# RaceSCH.net
KiCad netlist of a schematic drawn in Altium Designer
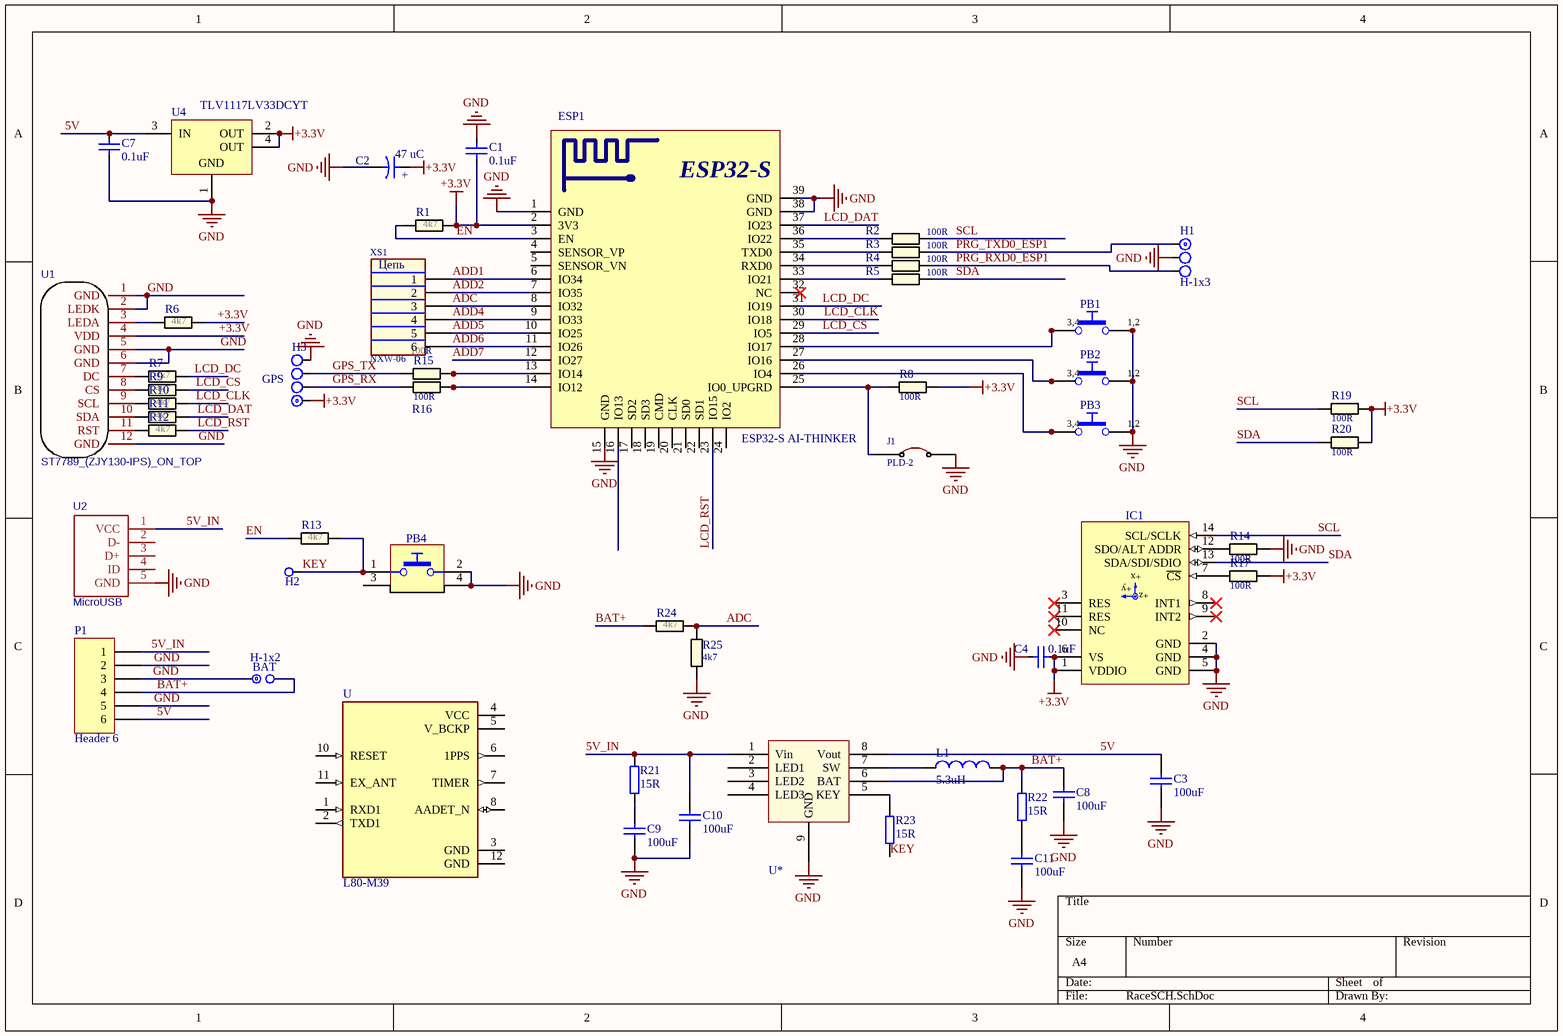
[diagram p0: RaceSCH.SchDoc]

(export (version "E")
  (design (tool "Eeschema 10.0.6"))
  (components
    (comp (ref "BAT") (value "H-1x2") (footprint "J1x2") (libsource (lib "Connektor") (part "H-1x2")))
    (comp (ref "C1")
      (value "0.1uF")
      (footprint "C0603")
      (description "Конденсатор")
      (libsource (lib "LoadControl") (part "CAPACITOR"))
    )
    (comp (ref "C2")
      (value "47 uC")
      (footprint "CAPMP3528X210N")
      (description "Polarised capacitor")
      (fields
        (field (name "PART NUMBER") "CTE3528-21_100UF_6.3V_10%")
        (field (name "VOLTAGE") "6.3V")
        (field (name "AUTHOR") "CERN DEM JLC")
      )
      (libsource (lib "Capacitors") (part "Capacitor - polarized"))
    )
    (comp (ref "C3")
      (value "100uF")
      (footprint "CAP1210")
      (description "CAP SM 1210 X5R 100uF 6.3V 10%")
      (fields
        (field (name "PART NUMBER") "CAP-SM-1210-X5R-100uF-6.3V")
        (field (name "MANUFACTURER") "GENERIC")
      )
      (libsource (lib "electronpowered") (part "CAP"))
    )
    (comp (ref "C4")
      (value "0.1uF")
      (footprint "C0603")
      (description "Конденсатор")
      (libsource (lib "LoadControl") (part "CAPACITOR"))
    )
    (comp (ref "C7")
      (value "0.1uF")
      (footprint "C0603")
      (description "Конденсатор")
      (libsource (lib "LoadControl") (part "CAPACITOR"))
    )
    (comp (ref "C8")
      (value "100uF")
      (footprint "CAP1210")
      (description "CAP SM 1210 X5R 100uF 6.3V 10%")
      (fields
        (field (name "PART NUMBER") "CAP-SM-1210-X5R-100uF-6.3V")
        (field (name "MANUFACTURER") "GENERIC")
      )
      (libsource (lib "electronpowered") (part "CAP"))
    )
    (comp (ref "C9")
      (value "100uF")
      (footprint "CAP1210")
      (description "CAP SM 1210 X5R 100uF 6.3V 10%")
      (fields
        (field (name "PART NUMBER") "CAP-SM-1210-X5R-100uF-6.3V")
        (field (name "MANUFACTURER") "GENERIC")
      )
      (libsource (lib "electronpowered") (part "CAP"))
    )
    (comp (ref "C10")
      (value "100uF")
      (footprint "CAP1210")
      (description "CAP SM 1210 X5R 100uF 6.3V 10%")
      (fields
        (field (name "PART NUMBER") "CAP-SM-1210-X5R-100uF-6.3V")
        (field (name "MANUFACTURER") "GENERIC")
      )
      (libsource (lib "electronpowered") (part "CAP"))
    )
    (comp (ref "C11")
      (value "100uF")
      (footprint "CAP1210")
      (description "CAP SM 1210 X5R 100uF 6.3V 10%")
      (fields
        (field (name "PART NUMBER") "CAP-SM-1210-X5R-100uF-6.3V")
        (field (name "MANUFACTURER") "GENERIC")
      )
      (libsource (lib "electronpowered") (part "CAP"))
    )
    (comp (ref "ESP1")
      (value "ESP32-S AI-THINKER")
      (footprint "ESP32-S")
      (description "Wi-Fi module")
      (libsource (lib "LoadControl") (part "ESP32-S AI-THINKER"))
    )
    (comp (ref "H1") (value "H-1x3") (footprint "J1x3") (libsource (lib "Connektor") (part "H-1x3")))
    (comp (ref "H2") (value "H-1") (footprint "J1") (libsource (lib "Connektor") (part "H-1")))
    (comp (ref "H3") (value "GPS") (footprint "J1x4") (libsource (lib "Connektor") (part "H-1x4")))
    (comp (ref "IC1")
      (value "ADXL343BCCZ")
      (footprint "ANALOG-DEVICES_CC-14-1")
      (description "3-Axis, ±2g/±4g/±8g/±16g Digital MEMS Accelerometer")
      (fields (field (name "MANUFACTURER") "ANALOG DEVICES") (field (name "AUTHOR") "CERN DEM JLC"))
      (libsource (lib "ICs And Semiconductors") (part "ADXL343"))
    )
    (comp (ref "J1") (value "PLD-2") (footprint "PLD-2") (libsource (lib "LoadControl") (part "PLD-2")))
    (comp (ref "L1")
      (value "5.3uH")
      (footprint "SRR5028-4R2Y")
      (fields (field (name "Comment") "INDUCTOR_2"))
      (libsource (lib "FlowMetter") (part "INDUCTOR_2"))
    )
    (comp (ref "P1")
      (value "Header 6")
      (footprint "HDR1X6")
      (description "Header, 6-Pin")
      (fields (field (name "PUBLISHER") "Altium Limited"))
      (libsource (lib "Miscellaneous Connectors") (part "Header 6"))
    )
    (comp (ref "PB1")
      (value "Push Button")
      (footprint "PB_OMRON_B3F-1000")
      (description "Push-Button Switch SPDT")
      (fields
        (field (name "PART NUMBER") "PB_OMRON_B3F-1000")
        (field (name "MANUFACTURER") "OMRON")
        (field (name "AUTHOR") "CERN DEM JMW")
      )
      (libsource (lib "Eletro-mechanical") (part "PB SPST 12NO-34NO"))
    )
    (comp (ref "PB2")
      (value "Push Button")
      (footprint "PB_OMRON_B3F-1000")
      (description "Push-Button Switch SPDT")
      (fields
        (field (name "PART NUMBER") "PB_OMRON_B3F-1000")
        (field (name "MANUFACTURER") "OMRON")
        (field (name "AUTHOR") "CERN DEM JMW")
      )
      (libsource (lib "Eletro-mechanical") (part "PB SPST 12NO-34NO"))
    )
    (comp (ref "PB3")
      (value "Push Button")
      (footprint "PB_OMRON_B3F-1000")
      (description "Push-Button Switch SPDT")
      (fields
        (field (name "PART NUMBER") "PB_OMRON_B3F-1000")
        (field (name "MANUFACTURER") "OMRON")
        (field (name "AUTHOR") "CERN DEM JMW")
      )
      (libsource (lib "Eletro-mechanical") (part "PB SPST 12NO-34NO"))
    )
    (comp (ref "PB4")
      (value "Push Button")
      (footprint "PB_ALPS_SKHHLQA010")
      (description "Push-Button Switch SPDT")
      (fields
        (field (name "PART NUMBER") "PB_ALPS_SKHHLQA010")
        (field (name "MANUFACTURER") "ALPS")
        (field (name "AUTHOR") "CERN DEM JLC")
      )
      (libsource (lib "Eletro-mechanical") (part "PB SPST 1NO-2NO 34CASE"))
    )
    (comp (ref "R1")
      (value "4k7")
      (footprint "R0603(1608)")
      (description "Resistor")
      (fields (field (name "Comment") "RESISTOR"))
      (libsource (lib "") (part "RESISTOR_1"))
    )
    (comp (ref "R2")
      (value "100R")
      (footprint "R0603(1608)")
      (description "Resistor")
      (fields (field (name "Comment") "RESISTOR"))
      (libsource (lib "") (part "RESISTOR_2"))
    )
    (comp (ref "R3")
      (value "100R")
      (footprint "R0603(1608)")
      (description "Resistor")
      (fields (field (name "Comment") "RESISTOR"))
      (libsource (lib "") (part "RESISTOR_2"))
    )
    (comp (ref "R4")
      (value "100R")
      (footprint "R0603(1608)")
      (description "Resistor")
      (fields (field (name "Comment") "RESISTOR"))
      (libsource (lib "") (part "RESISTOR_2"))
    )
    (comp (ref "R5")
      (value "100R")
      (footprint "R0603(1608)")
      (description "Resistor")
      (fields (field (name "Comment") "RESISTOR"))
      (libsource (lib "") (part "RESISTOR_2"))
    )
    (comp (ref "R6")
      (value "4k7")
      (footprint "R0603(1608)")
      (description "Resistor")
      (fields (field (name "Comment") "RESISTOR"))
      (libsource (lib "") (part "RESISTOR_1"))
    )
    (comp (ref "R7")
      (value "4k7")
      (footprint "R0603(1608)")
      (description "Resistor")
      (fields (field (name "Comment") "RESISTOR"))
      (libsource (lib "") (part "RESISTOR_1"))
    )
    (comp (ref "R8")
      (value "100R")
      (footprint "R0603(1608)")
      (description "Resistor")
      (fields (field (name "Comment") "RESISTOR"))
      (libsource (lib "") (part "RESISTOR_1"))
    )
    (comp (ref "R9")
      (value "4k7")
      (footprint "R0603(1608)")
      (description "Resistor")
      (fields (field (name "Comment") "RESISTOR"))
      (libsource (lib "") (part "RESISTOR_1"))
    )
    (comp (ref "R10")
      (value "4k7")
      (footprint "R0603(1608)")
      (description "Resistor")
      (fields (field (name "Comment") "RESISTOR"))
      (libsource (lib "") (part "RESISTOR_1"))
    )
    (comp (ref "R11")
      (value "4k7")
      (footprint "R0603(1608)")
      (description "Resistor")
      (fields (field (name "Comment") "RESISTOR"))
      (libsource (lib "") (part "RESISTOR_1"))
    )
    (comp (ref "R12")
      (value "4k7")
      (footprint "R0603(1608)")
      (description "Resistor")
      (fields (field (name "Comment") "RESISTOR"))
      (libsource (lib "") (part "RESISTOR_1"))
    )
    (comp (ref "R13")
      (value "4k7")
      (footprint "R0603(1608)")
      (description "Resistor")
      (fields (field (name "Comment") "RESISTOR"))
      (libsource (lib "") (part "RESISTOR_1"))
    )
    (comp (ref "R14")
      (value "100R")
      (footprint "R0603(1608)")
      (description "Resistor")
      (fields (field (name "Comment") "RESISTOR"))
      (libsource (lib "") (part "RESISTOR_3"))
    )
    (comp (ref "R15")
      (value "100R")
      (footprint "R0603(1608)")
      (description "Resistor")
      (fields (field (name "Comment") "RESISTOR"))
      (libsource (lib "LoadControl") (part "RESISTOR"))
    )
    (comp (ref "R16")
      (value "100R")
      (footprint "R0603(1608)")
      (description "Resistor")
      (fields (field (name "Comment") "RESISTOR"))
      (libsource (lib "LoadControl") (part "RESISTOR"))
    )
    (comp (ref "R17")
      (value "100R")
      (footprint "R0603(1608)")
      (description "Resistor")
      (fields (field (name "Comment") "RESISTOR"))
      (libsource (lib "") (part "RESISTOR_1"))
    )
    (comp (ref "R19")
      (value "100R")
      (footprint "R0603(1608)")
      (description "Resistor")
      (fields (field (name "Comment") "RESISTOR"))
      (libsource (lib "") (part "RESISTOR_3"))
    )
    (comp (ref "R20")
      (value "100R")
      (footprint "R0603(1608)")
      (description "Resistor")
      (fields (field (name "Comment") "RESISTOR"))
      (libsource (lib "") (part "RESISTOR_3"))
    )
    (comp (ref "R21")
      (value "15R")
      (footprint "RES0603")
      (description "RES SM 0603 15R")
      (fields (field (name "PART NUMBER") "RES-SM-0603-15R") (field (name "MANUFACTURER") "GENERIC"))
      (libsource (lib "electronpowered") (part "RES"))
    )
    (comp (ref "R22")
      (value "15R")
      (footprint "RES0603")
      (description "RES SM 0603 15R")
      (fields (field (name "PART NUMBER") "RES-SM-0603-15R") (field (name "MANUFACTURER") "GENERIC"))
      (libsource (lib "electronpowered") (part "RES"))
    )
    (comp (ref "R23")
      (value "15R")
      (footprint "RES0603")
      (description "RES SM 0603 15R")
      (fields (field (name "PART NUMBER") "RES-SM-0603-15R") (field (name "MANUFACTURER") "GENERIC"))
      (libsource (lib "electronpowered") (part "RES"))
    )
    (comp (ref "R24")
      (value "4k7")
      (footprint "R0603(1608)")
      (description "Resistor")
      (fields (field (name "Comment") "RESISTOR"))
      (libsource (lib "") (part "RESISTOR_1"))
    )
    (comp (ref "R25")
      (value "4k7")
      (footprint "R0603(1608)")
      (description "Resistor")
      (fields (field (name "Comment") "RESISTOR"))
      (libsource (lib "LoadControl") (part "RESISTOR"))
    )
    (comp (ref "U")
      (value "L80-M39")
      (footprint "XCVR_L80-M39")
      (fields (field (name "MF") "Quectel"))
      (libsource (lib "L80-M39") (part "L80-M39"))
    )
    (comp (ref "U*")
      (value "IP5306")
      (footprint "IP5306_GND")
      (description "2.1A_lipo_CHARGER")
      (libsource (lib "MyLib") (part "IP5306"))
    )
    (comp (ref "U1")
      (value "ST7789_(ZJY130-IPS)_ON_TOP")
      (footprint "ST7789_ON_TOP")
      (fields
        (field (name "BOM_MANUFACTURER PART") "?")
        (field (name "BOM_SUPPLIER PART") "undefined")
        (field (name "CONTRIBUTOR") "§°§Э§Ц§Ф §¬§а§б§Ц§Ы§Ь§Ъ§Я")
      )
      (libsource (lib "LCD_LIB") (part "ST7789_(ZJY130-IPS)_ON_TOP copy"))
    )
    (comp (ref "U2")
      (value "MicroUSB")
      (footprint "MICROUSB")
      (fields (field (name "BOM_MANUFACTURER PART") "?") (field (name "CONTRIBUTOR") "SparkFun"))
      (libsource (lib "LCD_LIB") (part "MicroUSB"))
    )
    (comp (ref "U4")
      (value "TLV1117LV33DCYT")
      (footprint "TI-DCY4_N")
      (fields (field (name "MANUFACTURER") "Texas Instruments"))
      (libsource (lib "FlowMetter") (part "TLV1117LV30DCYT"))
    )
    (comp (ref "XS1")
      (value "NXW-06")
      (footprint "NXW-06")
      (description "2.0mm pitch")
      (libsource (lib "FlowMetter") (part "NXW-06"))
    )
  )
  (nets
    (net (code "1") (name "+3.3V") (class "Default")
      (node (ref "C1") (pin "2") (pinfunction "2_2") (pintype "passive"))
      (node (ref "C2") (pin "1") (pinfunction "1_1") (pintype "passive"))
      (node (ref "C4") (pin "1") (pinfunction "1_1") (pintype "passive"))
      (node (ref "ESP1") (pin "2") (pinfunction "3V3_2") (pintype "passive"))
      (node (ref "H3") (pin "1") (pinfunction "1_1") (pintype "passive"))
      (node (ref "IC1") (pin "1") (pinfunction "VDDIO_1") (pintype "power_in"))
      (node (ref "IC1") (pin "6") (pinfunction "VS_6") (pintype "power_in"))
      (node (ref "R1") (pin "2") (pintype "passive"))
      (node (ref "R17") (pin "2") (pintype "passive"))
      (node (ref "R19") (pin "1") (pintype "passive"))
      (node (ref "R20") (pin "1") (pintype "passive"))
      (node (ref "R6") (pin "2") (pintype "passive"))
      (node (ref "R8") (pin "2") (pintype "passive"))
      (node (ref "U1") (pin "4") (pinfunction "VDD_4") (pintype "passive"))
      (node (ref "U4") (pin "2") (pinfunction "OUT_2") (pintype "power_in"))
      (node (ref "U4") (pin "4") (pinfunction "OUT_4") (pintype "power_in"))
    )
    (net (code "2") (name "/5V") (class "Default")
      (node (ref "C3") (pin "2") (pinfunction "2_2") (pintype "passive"))
      (node (ref "C7") (pin "1") (pinfunction "1_1") (pintype "passive"))
      (node (ref "P1") (pin "6") (pinfunction "6_6") (pintype "passive"))
      (node (ref "U*") (pin "8") (pinfunction "Vout_8") (pintype "passive"))
      (node (ref "U4") (pin "3") (pinfunction "IN_3") (pintype "power_in"))
    )
    (net (code "3") (name "/5V_IN") (class "Default")
      (node (ref "C10") (pin "2") (pinfunction "2_2") (pintype "passive"))
      (node (ref "P1") (pin "1") (pinfunction "1_1") (pintype "passive"))
      (node (ref "R21") (pin "2") (pinfunction "2_2") (pintype "passive"))
      (node (ref "U*") (pin "1") (pinfunction "Vin_1") (pintype "passive"))
      (node (ref "U2") (pin "1") (pinfunction "VCC_1") (pintype "passive"))
    )
    (net (code "4") (name "/ADC") (class "Default")
      (node (ref "ESP1") (pin "8") (pinfunction "IO32_8") (pintype "power_in"))
      (node (ref "R24") (pin "2") (pintype "passive"))
      (node (ref "R25") (pin "2") (pintype "passive"))
      (node (ref "XS1") (pin "3") (pinfunction "3_3") (pintype "passive"))
    )
    (net (code "5") (name "/ADD1") (class "Default")
      (node (ref "ESP1") (pin "6") (pinfunction "IO34_6") (pintype "passive"))
      (node (ref "XS1") (pin "1") (pinfunction "1_1") (pintype "passive"))
    )
    (net (code "6") (name "/ADD2") (class "Default")
      (node (ref "ESP1") (pin "7") (pinfunction "IO35_7") (pintype "passive"))
      (node (ref "XS1") (pin "2") (pinfunction "2_2") (pintype "passive"))
    )
    (net (code "7") (name "/ADD4") (class "Default")
      (node (ref "ESP1") (pin "9") (pinfunction "IO33_9") (pintype "power_in"))
      (node (ref "XS1") (pin "4") (pinfunction "4_4") (pintype "passive"))
    )
    (net (code "8") (name "/ADD5") (class "Default")
      (node (ref "ESP1") (pin "10") (pinfunction "IO25_10") (pintype "power_in"))
      (node (ref "XS1") (pin "5") (pinfunction "5_5") (pintype "passive"))
    )
    (net (code "9") (name "/ADD6") (class "Default")
      (node (ref "ESP1") (pin "11") (pinfunction "IO26_11") (pintype "power_in"))
      (node (ref "XS1") (pin "6") (pinfunction "6_6") (pintype "passive"))
    )
    (net (code "10") (name "/ADD7") (class "Default")
      (node (ref "ESP1") (pin "12") (pinfunction "IO27_12") (pintype "power_in"))
    )
    (net (code "11") (name "/BAT+") (class "Default")
      (node (ref "BAT") (pin "2") (pinfunction "2_2") (pintype "passive"))
      (node (ref "C8") (pin "2") (pinfunction "2_2") (pintype "passive"))
      (node (ref "L1") (pin "2") (pinfunction "2_2") (pintype "passive"))
      (node (ref "P1") (pin "4") (pinfunction "4_4") (pintype "passive"))
      (node (ref "R22") (pin "2") (pinfunction "2_2") (pintype "passive"))
      (node (ref "R24") (pin "1") (pintype "passive"))
      (node (ref "U*") (pin "6") (pinfunction "BAT_6") (pintype "passive"))
    )
    (net (code "12") (name "/EN") (class "Default")
      (node (ref "ESP1") (pin "3") (pinfunction "EN_3") (pintype "passive"))
      (node (ref "R1") (pin "1") (pintype "passive"))
      (node (ref "R13") (pin "1") (pintype "passive"))
    )
    (net (code "13") (name "/GPS_RX") (class "Default")
      (node (ref "H3") (pin "2") (pinfunction "2_2") (pintype "passive"))
      (node (ref "R16") (pin "1") (pintype "passive"))
    )
    (net (code "14") (name "/GPS_TX") (class "Default")
      (node (ref "H3") (pin "3") (pinfunction "3_3") (pintype "passive"))
      (node (ref "R15") (pin "1") (pintype "passive"))
    )
    (net (code "15") (name "/KEY") (class "Default")
      (node (ref "H2") (pin "1") (pinfunction "1_1") (pintype "passive"))
      (node (ref "PB4") (pin "1") (pinfunction "1_1") (pintype "passive"))
      (node (ref "R13") (pin "2") (pintype "passive"))
      (node (ref "R23") (pin "1") (pinfunction "1_1") (pintype "passive"))
    )
    (net (code "16") (name "/LCD_CLK") (class "Default")
      (node (ref "ESP1") (pin "30") (pinfunction "IO18_30") (pintype "power_in"))
      (node (ref "R10") (pin "2") (pintype "passive"))
    )
    (net (code "17") (name "/LCD_CS") (class "Default")
      (node (ref "ESP1") (pin "29") (pinfunction "IO5_29") (pintype "power_in"))
      (node (ref "R9") (pin "2") (pintype "passive"))
    )
    (net (code "18") (name "/LCD_DAT") (class "Default")
      (node (ref "ESP1") (pin "37") (pinfunction "IO23_37") (pintype "power_in"))
      (node (ref "R11") (pin "2") (pintype "passive"))
    )
    (net (code "19") (name "/LCD_DC") (class "Default")
      (node (ref "ESP1") (pin "31") (pinfunction "IO19_31") (pintype "power_in"))
      (node (ref "R7") (pin "2") (pintype "passive"))
    )
    (net (code "20") (name "/LCD_RST") (class "Default")
      (node (ref "ESP1") (pin "23") (pinfunction "IO15_23") (pintype "power_in"))
      (node (ref "R12") (pin "2") (pintype "passive"))
    )
    (net (code "21") (name "/PRG_RXD0_ESP1") (class "Default")
      (node (ref "H1") (pin "3") (pinfunction "3_3") (pintype "passive"))
      (node (ref "R4") (pin "1") (pintype "passive"))
    )
    (net (code "22") (name "/PRG_TXD0_ESP1") (class "Default")
      (node (ref "H1") (pin "1") (pinfunction "1_1") (pintype "passive"))
      (node (ref "R3") (pin "1") (pintype "passive"))
    )
    (net (code "23") (name "/SCL") (class "Default")
      (node (ref "IC1") (pin "14") (pinfunction "SCL/SCLK_14") (pintype "input"))
      (node (ref "R19") (pin "2") (pintype "passive"))
      (node (ref "R2") (pin "1") (pintype "passive"))
    )
    (net (code "24") (name "/SDA") (class "Default")
      (node (ref "IC1") (pin "13") (pinfunction "SDA/SDI/SDIO_13") (pintype "bidirectional"))
      (node (ref "R20") (pin "2") (pintype "passive"))
      (node (ref "R5") (pin "1") (pintype "passive"))
    )
    (net (code "25") (name "GND") (class "Default")
      (node (ref "BAT") (pin "1") (pinfunction "1_1") (pintype "passive"))
      (node (ref "C1") (pin "1") (pinfunction "1_1") (pintype "passive"))
      (node (ref "C10") (pin "1") (pinfunction "1_1") (pintype "passive"))
      (node (ref "C11") (pin "1") (pinfunction "1_1") (pintype "passive"))
      (node (ref "C2") (pin "2") (pinfunction "2_2") (pintype "passive"))
      (node (ref "C3") (pin "1") (pinfunction "1_1") (pintype "passive"))
      (node (ref "C4") (pin "2") (pinfunction "2_2") (pintype "passive"))
      (node (ref "C7") (pin "2") (pinfunction "2_2") (pintype "passive"))
      (node (ref "C8") (pin "1") (pinfunction "1_1") (pintype "passive"))
      (node (ref "C9") (pin "1") (pinfunction "1_1") (pintype "passive"))
      (node (ref "ESP1") (pin "1") (pinfunction "GND_1") (pintype "passive"))
      (node (ref "ESP1") (pin "15") (pinfunction "GND_15") (pintype "power_in"))
      (node (ref "ESP1") (pin "38") (pinfunction "GND_38") (pintype "power_in"))
      (node (ref "ESP1") (pin "39") (pinfunction "GND_39") (pintype "power_in"))
      (node (ref "H1") (pin "2") (pinfunction "2_2") (pintype "passive"))
      (node (ref "H3") (pin "4") (pinfunction "4_4") (pintype "passive"))
      (node (ref "IC1") (pin "2") (pinfunction "GND_2") (pintype "power_in"))
      (node (ref "IC1") (pin "4") (pinfunction "GND_4") (pintype "power_in"))
      (node (ref "IC1") (pin "5") (pinfunction "GND_5") (pintype "power_in"))
      (node (ref "J1") (pin "2") (pinfunction "2_2") (pintype "power_in"))
      (node (ref "P1") (pin "2") (pinfunction "2_2") (pintype "passive"))
      (node (ref "P1") (pin "3") (pinfunction "3_3") (pintype "passive"))
      (node (ref "P1") (pin "5") (pinfunction "5_5") (pintype "passive"))
      (node (ref "PB1") (pin "1") (pinfunction "1_1") (pintype "passive"))
      (node (ref "PB1") (pin "2") (pinfunction "2_2") (pintype "passive"))
      (node (ref "PB2") (pin "1") (pinfunction "1_1") (pintype "passive"))
      (node (ref "PB2") (pin "2") (pinfunction "2_2") (pintype "passive"))
      (node (ref "PB3") (pin "1") (pinfunction "1_1") (pintype "passive"))
      (node (ref "PB3") (pin "2") (pinfunction "2_2") (pintype "passive"))
      (node (ref "PB4") (pin "2") (pinfunction "2_2") (pintype "passive"))
      (node (ref "PB4") (pin "4") (pinfunction "4_4") (pintype "passive"))
      (node (ref "R14") (pin "1") (pintype "passive"))
      (node (ref "R25") (pin "1") (pintype "passive"))
      (node (ref "U*") (pin "9") (pinfunction "GND_9") (pintype "passive"))
      (node (ref "U1") (pin "1") (pinfunction "GND_1") (pintype "passive"))
      (node (ref "U1") (pin "12") (pinfunction "GND_12") (pintype "passive"))
      (node (ref "U1") (pin "2") (pinfunction "LEDK_2") (pintype "passive"))
      (node (ref "U1") (pin "5") (pinfunction "GND_5") (pintype "passive"))
      (node (ref "U1") (pin "6") (pinfunction "GND_6") (pintype "passive"))
      (node (ref "U2") (pin "5") (pinfunction "GND_5") (pintype "passive"))
      (node (ref "U4") (pin "1") (pinfunction "GND_1") (pintype "power_in"))
    )
    (net (code "26") (name "Net-(C9-Pad2)") (class "Default")
      (node (ref "C9") (pin "2") (pinfunction "2_2") (pintype "passive"))
      (node (ref "R21") (pin "1") (pinfunction "1_1") (pintype "passive"))
    )
    (net (code "27") (name "Net-(C11-Pad2)") (class "Default")
      (node (ref "C11") (pin "2") (pinfunction "2_2") (pintype "passive"))
      (node (ref "R22") (pin "1") (pinfunction "1_1") (pintype "passive"))
    )
    (net (code "28") (name "Net-(ESP1-IO0_UPGRD)") (class "Default")
      (node (ref "ESP1") (pin "25") (pinfunction "IO0_UPGRD_25") (pintype "power_in"))
      (node (ref "J1") (pin "1") (pinfunction "1_1") (pintype "power_in"))
      (node (ref "R8") (pin "1") (pintype "passive"))
    )
    (net (code "29") (name "Net-(ESP1-IO4)") (class "Default")
      (node (ref "ESP1") (pin "26") (pinfunction "IO4_26") (pintype "power_in"))
      (node (ref "PB3") (pin "3") (pinfunction "3_3") (pintype "passive"))
      (node (ref "PB3") (pin "4") (pinfunction "4_4") (pintype "passive"))
    )
    (net (code "30") (name "Net-(ESP1-IO12)") (class "Default")
      (node (ref "ESP1") (pin "14") (pinfunction "IO12_14") (pintype "power_in"))
      (node (ref "R16") (pin "2") (pintype "passive"))
    )
    (net (code "31") (name "Net-(ESP1-IO14)") (class "Default")
      (node (ref "ESP1") (pin "13") (pinfunction "IO14_13") (pintype "power_in"))
      (node (ref "R15") (pin "2") (pintype "passive"))
    )
    (net (code "32") (name "Net-(ESP1-IO16)") (class "Default")
      (node (ref "ESP1") (pin "27") (pinfunction "IO16_27") (pintype "power_in"))
      (node (ref "PB2") (pin "3") (pinfunction "3_3") (pintype "passive"))
      (node (ref "PB2") (pin "4") (pinfunction "4_4") (pintype "passive"))
    )
    (net (code "33") (name "Net-(ESP1-IO17)") (class "Default")
      (node (ref "ESP1") (pin "28") (pinfunction "IO17_28") (pintype "power_in"))
      (node (ref "PB1") (pin "3") (pinfunction "3_3") (pintype "passive"))
      (node (ref "PB1") (pin "4") (pinfunction "4_4") (pintype "passive"))
    )
    (net (code "34") (name "Net-(ESP1-IO21)") (class "Default")
      (node (ref "ESP1") (pin "33") (pinfunction "IO21_33") (pintype "power_in"))
      (node (ref "R5") (pin "2") (pintype "passive"))
    )
    (net (code "35") (name "Net-(ESP1-IO22)") (class "Default")
      (node (ref "ESP1") (pin "36") (pinfunction "IO22_36") (pintype "power_in"))
      (node (ref "R2") (pin "2") (pintype "passive"))
    )
    (net (code "36") (name "Net-(ESP1-RXD0)") (class "Default")
      (node (ref "ESP1") (pin "34") (pinfunction "RXD0_34") (pintype "power_in"))
      (node (ref "R4") (pin "2") (pintype "passive"))
    )
    (net (code "37") (name "Net-(ESP1-TXD0)") (class "Default")
      (node (ref "ESP1") (pin "35") (pinfunction "TXD0_35") (pintype "power_in"))
      (node (ref "R3") (pin "2") (pintype "passive"))
    )
    (net (code "38") (name "Net-(IC1-SDO{slash}ALT_ADDR)") (class "Default")
      (node (ref "IC1") (pin "12") (pinfunction "SDO/ALT_ADDR_12") (pintype "bidirectional"))
      (node (ref "R14") (pin "2") (pintype "passive"))
    )
    (net (code "39") (name "Net-(IC1-~{CS})") (class "Default")
      (node (ref "IC1") (pin "7") (pinfunction "~{CS}_7") (pintype "input"))
      (node (ref "R17") (pin "1") (pintype "passive"))
    )
    (net (code "40") (name "Net-(U*-KEY)") (class "Default")
      (node (ref "R23") (pin "2") (pinfunction "2_2") (pintype "passive"))
      (node (ref "U*") (pin "5") (pinfunction "KEY_5") (pintype "passive"))
    )
    (net (code "41") (name "Net-(U*-SW)") (class "Default")
      (node (ref "L1") (pin "1") (pinfunction "1_1") (pintype "passive"))
      (node (ref "U*") (pin "7") (pinfunction "SW_7") (pintype "passive"))
    )
    (net (code "42") (name "Net-(U1-CS)") (class "Default")
      (node (ref "R9") (pin "1") (pintype "passive"))
      (node (ref "U1") (pin "8") (pinfunction "CS_8") (pintype "passive"))
    )
    (net (code "43") (name "Net-(U1-DC)") (class "Default")
      (node (ref "R7") (pin "1") (pintype "passive"))
      (node (ref "U1") (pin "7") (pinfunction "DC_7") (pintype "passive"))
    )
    (net (code "44") (name "Net-(U1-LEDA)") (class "Default")
      (node (ref "R6") (pin "1") (pintype "passive"))
      (node (ref "U1") (pin "3") (pinfunction "LEDA_3") (pintype "passive"))
    )
    (net (code "45") (name "Net-(U1-RST)") (class "Default")
      (node (ref "R12") (pin "1") (pintype "passive"))
      (node (ref "U1") (pin "11") (pinfunction "RST_11") (pintype "passive"))
    )
    (net (code "46") (name "Net-(U1-SCL)") (class "Default")
      (node (ref "R10") (pin "1") (pintype "passive"))
      (node (ref "U1") (pin "9") (pinfunction "SCL_9") (pintype "passive"))
    )
    (net (code "47") (name "Net-(U1-SDA)") (class "Default")
      (node (ref "R11") (pin "1") (pintype "passive"))
      (node (ref "U1") (pin "10") (pinfunction "SDA_10") (pintype "passive"))
    )
    (net (code "48") (name "unconnected-(ESP1-CLK-Pad20)") (class "Default")
      (node (ref "ESP1") (pin "20") (pinfunction "CLK_20") (pintype "power_in"))
    )
    (net (code "49") (name "unconnected-(ESP1-CMD-Pad19)") (class "Default")
      (node (ref "ESP1") (pin "19") (pinfunction "CMD_19") (pintype "power_in"))
    )
    (net (code "50") (name "unconnected-(ESP1-IO2-Pad24)") (class "Default")
      (node (ref "ESP1") (pin "24") (pinfunction "IO2_24") (pintype "power_in"))
    )
    (net (code "51") (name "unconnected-(ESP1-IO13-Pad16)") (class "Default")
      (node (ref "ESP1") (pin "16") (pinfunction "IO13_16") (pintype "power_in"))
    )
    (net (code "52") (name "unconnected-(ESP1-NC-Pad32)") (class "Default")
      (node (ref "ESP1") (pin "32") (pinfunction "NC_32") (pintype "power_in+no_connect"))
    )
    (net (code "53") (name "unconnected-(ESP1-SD0-Pad21)") (class "Default")
      (node (ref "ESP1") (pin "21") (pinfunction "SD0_21") (pintype "power_in"))
    )
    (net (code "54") (name "unconnected-(ESP1-SD1-Pad22)") (class "Default")
      (node (ref "ESP1") (pin "22") (pinfunction "SD1_22") (pintype "power_in"))
    )
    (net (code "55") (name "unconnected-(ESP1-SD2-Pad17)") (class "Default")
      (node (ref "ESP1") (pin "17") (pinfunction "SD2_17") (pintype "power_in"))
    )
    (net (code "56") (name "unconnected-(ESP1-SD3-Pad18)") (class "Default")
      (node (ref "ESP1") (pin "18") (pinfunction "SD3_18") (pintype "power_in"))
    )
    (net (code "57") (name "unconnected-(ESP1-SENSOR_VN-Pad5)") (class "Default")
      (node (ref "ESP1") (pin "5") (pinfunction "SENSOR_VN_5") (pintype "passive"))
    )
    (net (code "58") (name "unconnected-(ESP1-SENSOR_VP-Pad4)") (class "Default")
      (node (ref "ESP1") (pin "4") (pinfunction "SENSOR_VP_4") (pintype "passive"))
    )
    (net (code "59") (name "unconnected-(IC1-INT1-Pad8)") (class "Default")
      (node (ref "IC1") (pin "8") (pinfunction "INT1_8") (pintype "output+no_connect"))
    )
    (net (code "60") (name "unconnected-(IC1-INT2-Pad9)") (class "Default")
      (node (ref "IC1") (pin "9") (pinfunction "INT2_9") (pintype "output+no_connect"))
    )
    (net (code "61") (name "unconnected-(IC1-NC-Pad10)") (class "Default")
      (node (ref "IC1") (pin "10") (pinfunction "NC_10") (pintype "passive+no_connect"))
    )
    (net (code "62") (name "unconnected-(IC1-RES-Pad3)") (class "Default")
      (node (ref "IC1") (pin "3") (pinfunction "RES_3") (pintype "passive+no_connect"))
    )
    (net (code "63") (name "unconnected-(IC1-RES-Pad11)") (class "Default")
      (node (ref "IC1") (pin "11") (pinfunction "RES_11") (pintype "passive+no_connect"))
    )
    (net (code "64") (name "unconnected-(PB4-Pad3)") (class "Default")
      (node (ref "PB4") (pin "3") (pinfunction "3_3") (pintype "passive"))
    )
    (net (code "65") (name "unconnected-(U*-LED1-Pad2)") (class "Default")
      (node (ref "U*") (pin "2") (pinfunction "LED1_2") (pintype "passive"))
    )
    (net (code "66") (name "unconnected-(U*-LED2-Pad3)") (class "Default")
      (node (ref "U*") (pin "3") (pinfunction "LED2_3") (pintype "passive"))
    )
    (net (code "67") (name "unconnected-(U*-LED3-Pad4)") (class "Default")
      (node (ref "U*") (pin "4") (pinfunction "LED3_4") (pintype "passive"))
    )
    (net (code "68") (name "unconnected-(U-1PPS-Pad6)") (class "Default")
      (node (ref "U") (pin "6") (pinfunction "1PPS_6") (pintype "output"))
    )
    (net (code "69") (name "unconnected-(U-AADET_N-Pad8)") (class "Default")
      (node (ref "U") (pin "8") (pinfunction "AADET_N_8") (pintype "bidirectional"))
    )
    (net (code "70") (name "unconnected-(U-EX_ANT-Pad11)") (class "Default")
      (node (ref "U") (pin "11") (pinfunction "EX_ANT_11") (pintype "input"))
    )
    (net (code "71") (name "unconnected-(U-GND-Pad3)") (class "Default")
      (node (ref "U") (pin "3") (pinfunction "GND_3") (pintype "power_in"))
    )
    (net (code "72") (name "unconnected-(U-GND-Pad12)") (class "Default")
      (node (ref "U") (pin "12") (pinfunction "GND_12") (pintype "power_in"))
    )
    (net (code "73") (name "unconnected-(U-RESET-Pad10)") (class "Default")
      (node (ref "U") (pin "10") (pinfunction "RESET_10") (pintype "input"))
    )
    (net (code "74") (name "unconnected-(U-RXD1-Pad1)") (class "Default")
      (node (ref "U") (pin "1") (pinfunction "RXD1_1") (pintype "input"))
    )
    (net (code "75") (name "unconnected-(U-TIMER-Pad7)") (class "Default")
      (node (ref "U") (pin "7") (pinfunction "TIMER_7") (pintype "output"))
    )
    (net (code "76") (name "unconnected-(U-TXD1-Pad2)") (class "Default")
      (node (ref "U") (pin "2") (pinfunction "TXD1_2") (pintype "output"))
    )
    (net (code "77") (name "unconnected-(U-VCC-Pad4)") (class "Default")
      (node (ref "U") (pin "4") (pinfunction "VCC_4") (pintype "power_in"))
    )
    (net (code "78") (name "unconnected-(U-V_BCKP-Pad5)") (class "Default")
      (node (ref "U") (pin "5") (pinfunction "V_BCKP_5") (pintype "power_in"))
    )
    (net (code "79") (name "unconnected-(U2-D+-Pad3)") (class "Default")
      (node (ref "U2") (pin "3") (pinfunction "D+_3") (pintype "passive"))
    )
    (net (code "80") (name "unconnected-(U2-D--Pad2)") (class "Default")
      (node (ref "U2") (pin "2") (pinfunction "D-_2") (pintype "passive"))
    )
    (net (code "81") (name "unconnected-(U2-ID-Pad4)") (class "Default")
      (node (ref "U2") (pin "4") (pinfunction "ID_4") (pintype "passive"))
    )
  )
)
